# RTerm.net
KiCad netlist of a schematic drawn in Altium Designer
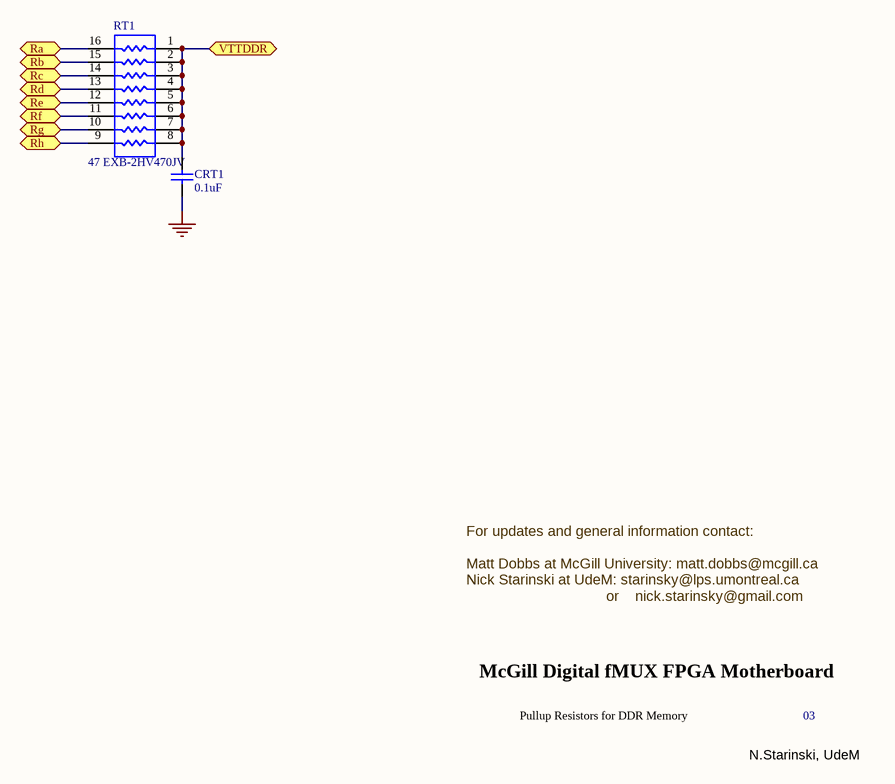
[diagram p0: RTerm.SchDoc]

(export (version "E")
  (design (tool "Eeschema 10.0.6"))
  (components
    (comp (ref "CRT1")
      (value "0.1uF")
      (footprint "CC1608-0603")
      (description "Capacitor (Semiconductor SIM Model)")
      (fields (field (name "PUBLISHER") "Altium Limited"))
      (libsource (lib "Miscellaneous Devices 02") (part "Cap Semi"))
    )
    (comp (ref "RT1")
      (value "47 EXB-2HV470JV")
      (footprint "0402_Array_2HV")
      (description "Isolated Resistor Network")
      (fields (field (name "PUBLISHER") "Altium Limited"))
      (libsource (lib "Miscellaneous Devices 02") (part "Res Pack3"))
    )
  )
  (nets
    (net (code "1") (name "/Ra") (class "Default")
      (node (ref "RT1") (pin "16") (pinfunction "16_16") (pintype "passive"))
    )
    (net (code "2") (name "/Rb") (class "Default")
      (node (ref "RT1") (pin "15") (pinfunction "15_15") (pintype "passive"))
    )
    (net (code "3") (name "/Rc") (class "Default")
      (node (ref "RT1") (pin "14") (pinfunction "14_14") (pintype "passive"))
    )
    (net (code "4") (name "/Rd") (class "Default")
      (node (ref "RT1") (pin "13") (pinfunction "13_13") (pintype "passive"))
    )
    (net (code "5") (name "/Re") (class "Default")
      (node (ref "RT1") (pin "12") (pinfunction "12_12") (pintype "passive"))
    )
    (net (code "6") (name "/Rf") (class "Default")
      (node (ref "RT1") (pin "11") (pinfunction "11_11") (pintype "passive"))
    )
    (net (code "7") (name "/Rg") (class "Default")
      (node (ref "RT1") (pin "10") (pinfunction "10_10") (pintype "passive"))
    )
    (net (code "8") (name "/Rh") (class "Default")
      (node (ref "RT1") (pin "9") (pinfunction "9_9") (pintype "passive"))
    )
    (net (code "9") (name "/VTTDDR") (class "Default")
      (node (ref "CRT1") (pin "2") (pinfunction "2_2") (pintype "passive"))
      (node (ref "RT1") (pin "1") (pinfunction "1_1") (pintype "passive"))
      (node (ref "RT1") (pin "2") (pinfunction "2_2") (pintype "passive"))
      (node (ref "RT1") (pin "3") (pinfunction "3_3") (pintype "passive"))
      (node (ref "RT1") (pin "4") (pinfunction "4_4") (pintype "passive"))
      (node (ref "RT1") (pin "5") (pinfunction "5_5") (pintype "passive"))
      (node (ref "RT1") (pin "6") (pinfunction "6_6") (pintype "passive"))
      (node (ref "RT1") (pin "7") (pinfunction "7_7") (pintype "passive"))
      (node (ref "RT1") (pin "8") (pinfunction "8_8") (pintype "passive"))
    )
    (net (code "10") (name "GND") (class "Default")
      (node (ref "CRT1") (pin "1") (pinfunction "1_1") (pintype "passive"))
    )
  )
)
